# Main.net
KiCad netlist of a schematic drawn in Altium Designer
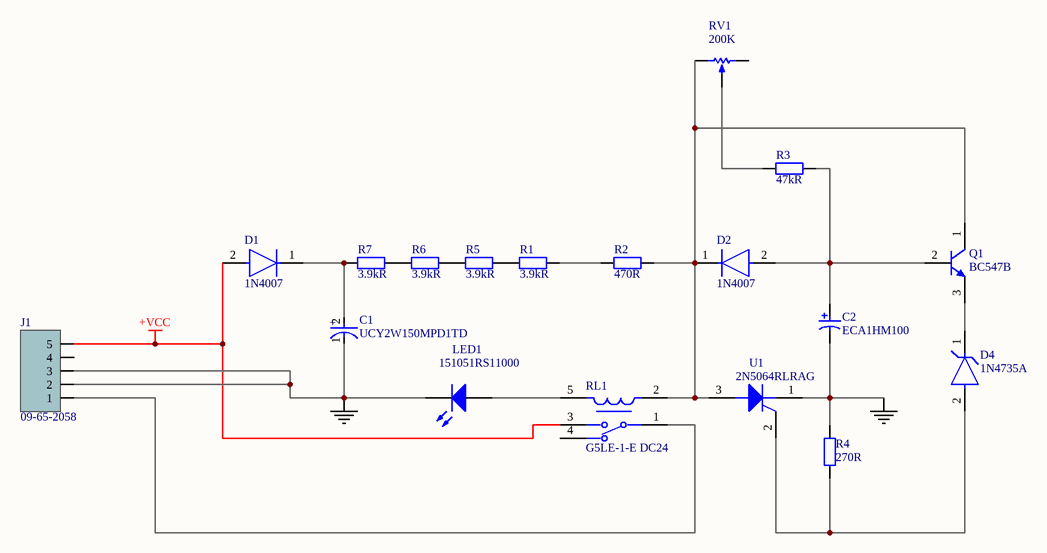
[diagram p0: Main.SchDoc]

(export (version "E")
  (design (tool "Eeschema 10.0.6"))
  (components
    (comp (ref "C1")
      (value "UCY2W150MPD1TD")
      (footprint "FP-UCY2W150MPD1TD-MFG")
      (description "CAP ALUM 15UF 20% 450V RADIAL")
      (fields (field (name "TOLERANCE") "20%"))
      (libsource (lib "Altium Content Vault") (part "a00bbbee19879c290e62620ae7e47b1"))
    )
    (comp (ref "C2")
      (value "ECA1HM100")
      (footprint "CAPPR55-200-1100X500X1200")
      (description "Aluminum Electrolytic Capacitor, 10 uF, +/- 20%, 50 V, -40 to 85 degC, 2-Pin THD, RoHS, Bulk")
      (fields (field (name "MANUFACTURER") "Panasonic") (field (name "TOLERANCE") "20%"))
      (libsource (lib "Altium Content Vault") (part "CAP-P-2"))
    )
    (comp (ref "D1")
      (value "1N4007")
      (footprint "FP-1N4007-MFG")
      (description "Rectifier diode 1000 V 1 A DO-41, ,")
      (fields
        (field (name "MANUFACTURER") "Diotec")
        (field (name "OCTOPART") "https://octopart.com/1n4007-diotec-4040411")
      )
      (libsource (lib "Altium Content Vault") (part "d7152d700b627762746794eb795d46e"))
    )
    (comp (ref "D2")
      (value "1N4007")
      (footprint "FP-1N4007-MFG")
      (description "Rectifier diode 1000 V 1 A DO-41, ,")
      (fields
        (field (name "MANUFACTURER") "Diotec")
        (field (name "OCTOPART") "https://octopart.com/1n4007-diotec-4040411")
      )
      (libsource (lib "Altium Content Vault") (part "d7152d700b627762746794eb795d46e"))
    )
    (comp (ref "D4")
      (value "1N4735A")
      (footprint "FP-017AH-MFG")
      (description "DIODE ZENER 6.2V 1W DO41")
      (fields
        (field (name "MANUFACTURER") "ON Semiconductor")
        (field (name "OCTOPART") "https://octopart.com/1n4735a-on+semiconductor-3533934")
      )
      (libsource (lib "Altium Content Vault") (part "f813f71cba58e380607f5dd3caf9714"))
    )
    (comp (ref "J1")
      (value "09652058")
      (footprint "09652058")
      (description "SPOX™ and KK® 396 Wire-to-Board Header, Vertical, with Friction Lock, 5 Circuits")
      (fields (field (name "MANUFACTURER") "Molex") (field (name "MANUFACTURER PART NUMBER") "09-65-2058"))
      (libsource (lib "Schlib") (part "09652058"))
    )
    (comp (ref "LED1")
      (value "151051RS11000")
      (footprint "Type 5mm")
      (description "THT LED round mono-color color lens, WL-TMRW, Red")
      (fields (field (name "MANUFACTURER") "Wuerth Elektronik"))
      (libsource (lib "Altium Content Vault") (part "WE-LED_K1A2-2"))
    )
    (comp (ref "Q1")
      (value "BC547B")
      (footprint "ONSC-TO-92-3-29-11")
      (description "Amplifier Transistor, NPN Silicon, 3-Pin TO-92, Bulk Box")
      (fields (field (name "MANUFACTURER") "On Semiconductor") (field (name "PARTNUMBER") "BC547C"))
      (libsource (lib "Altium Content Vault") (part "ONSC-NPN-C1B2E3-3"))
    )
    (comp (ref "R1")
      (value "PR02000203901JA100")
      (footprint "AXIAL-0.7")
      (description "PR02 Series Axial Metal Film Resistor 3.9kOhms +/-5% 2W +/-250ppm/degC")
      (fields
        (field (name "MANUFACTURER") "Vishay")
        (field (name "RESISTANCE") "3.9kR")
        (field (name "TOLERANCE") "5%")
        (field (name "PUBLISHER") "Altium Limited")
      )
      (libsource (lib "Miscellaneous Devices") (part "Res2"))
    )
    (comp (ref "R2")
      (value "470R")
      (footprint "AXIAL-0.4")
      (description "470 Ohms ±5% 0.5W, 1/2W Through Hole Resistor Axial - Metal Film")
      (fields
        (field (name "MANUFACTURER") "Vishay BCcomponents")
        (field (name "MANUFACTURER PART NUMBER") "SFR16S0004700JA500")
        (field (name "PUBLISHER") "Altium Limited")
      )
      (libsource (lib "Miscellaneous Devices") (part "Res2"))
    )
    (comp (ref "R3")
      (value "47kR")
      (footprint "AXIAL-0.4")
      (description "Res Metal Film 47K Ohm 1% 1/4W ±100ppm/°C Conformal AXL Thru-Hole T/R")
      (fields
        (field (name "MANUFACTURER") "Stackpole Electronics")
        (field (name "MANUFACTURER PART NUMBER") "RNF14FTD47K0")
        (field (name "PUBLISHER") "Altium Limited")
      )
      (libsource (lib "Miscellaneous Devices") (part "Res2"))
    )
    (comp (ref "R4")
      (value "SFR16S0002700JA500")
      (footprint "AXIAL-0.4")
      (fields
        (field (name "MANUFACTURER") "Vishay BCcomponents")
        (field (name "RESISTANCE") "270R")
        (field (name "TOLERANCE") "5%")
        (field (name "PUBLISHER") "Altium Limited")
      )
      (libsource (lib "") (part "Res2_2"))
    )
    (comp (ref "R5")
      (value "PR02000203901JA100")
      (footprint "AXIAL-0.7")
      (description "PR02 Series Axial Metal Film Resistor 3.9kOhms +/-5% 2W +/-250ppm/degC")
      (fields
        (field (name "MANUFACTURER") "Vishay")
        (field (name "RESISTANCE") "3.9kR")
        (field (name "TOLERANCE") "5%")
        (field (name "PUBLISHER") "Altium Limited")
      )
      (libsource (lib "") (part "Res2_1"))
    )
    (comp (ref "R6")
      (value "PR02000203901JA100")
      (footprint "AXIAL-0.7")
      (description "PR02 Series Axial Metal Film Resistor 3.9kOhms +/-5% 2W +/-250ppm/degC")
      (fields
        (field (name "MANUFACTURER") "Vishay")
        (field (name "RESISTANCE") "3.9kR")
        (field (name "TOLERANCE") "5%")
        (field (name "PUBLISHER") "Altium Limited")
      )
      (libsource (lib "Miscellaneous Devices") (part "Res2"))
    )
    (comp (ref "R7")
      (value "PR02000203901JA100")
      (footprint "AXIAL-0.7")
      (description "PR02 Series Axial Metal Film Resistor 3.9kOhms +/-5% 2W +/-250ppm/degC")
      (fields
        (field (name "MANUFACTURER") "Vishay")
        (field (name "RESISTANCE") "3.9kR")
        (field (name "TOLERANCE") "5%")
        (field (name "PUBLISHER") "Altium Limited")
      )
      (libsource (lib "") (part "Res2_1"))
    )
    (comp (ref "RL1")
      (value "G5LE-1-E DC24")
      (footprint "FP-G5LE-1-E_DC24-MFG")
      (description "RELAY GEN PURPOSE SPDT 16A 24V")
      (libsource (lib "Altium Content Vault") (part "c03b8d08e5d02e70a6880f365e34168"))
    )
    (comp (ref "RV1")
      (value "200K")
      (footprint "HDR1X2")
      (description "P160 Series 200 kOhm ±20 % Panel Mount Multi-Turn Potentiometer")
      (fields
        (field (name "MANUFACTURER") "TT BI")
        (field (name "MANUFACTURER PART NUMBER") "P160KNP-0QC15B200K")
        (field (name "PUBLISHER") "Altium Limited")
      )
      (libsource (lib "Miscellaneous Devices") (part "RPot"))
    )
    (comp (ref "U1")
      (value "2N5064RLRAG")
      (footprint "ONSC-TO-92-3-29-11")
      (fields (field (name "MANUFACTURER") "On Semiconductor"))
      (libsource (lib "Altium Content Vault") (part "ONSC-SCR-K1G2A3-3"))
    )
  )
  (nets
    (net (code "1") (name "+VCC") (class "Default")
      (node (ref "D1") (pin "2") (pinfunction "A_2") (pintype "passive"))
      (node (ref "J1") (pin "5") (pinfunction "5_5") (pintype "passive"))
      (node (ref "RL1") (pin "3") (pinfunction "3_3") (pintype "passive"))
    )
    (net (code "2") (name "GND") (class "Default")
      (node (ref "C1") (pin "1") (pinfunction "C_1") (pintype "passive"))
      (node (ref "C2") (pin "2") (pinfunction "2_2") (pintype "passive"))
      (node (ref "J1") (pin "2") (pinfunction "2_2") (pintype "passive"))
      (node (ref "J1") (pin "3") (pinfunction "3_3") (pintype "passive"))
      (node (ref "LED1") (pin "1") (pinfunction "K_1") (pintype "passive"))
      (node (ref "R4") (pin "2") (pinfunction "2_2") (pintype "passive"))
      (node (ref "U1") (pin "1") (pinfunction "K_1") (pintype "passive"))
    )
    (net (code "3") (name "Net-(C1-A)") (class "Default")
      (node (ref "C1") (pin "2") (pinfunction "A_2") (pintype "passive"))
      (node (ref "D1") (pin "1") (pinfunction "C_1") (pintype "passive"))
      (node (ref "R7") (pin "2") (pinfunction "2_2") (pintype "passive"))
    )
    (net (code "4") (name "Net-(D2-A)") (class "Default")
      (node (ref "C2") (pin "1") (pinfunction "1_1") (pintype "passive"))
      (node (ref "D2") (pin "2") (pinfunction "A_2") (pintype "passive"))
      (node (ref "Q1") (pin "2") (pinfunction "B_2") (pintype "passive"))
      (node (ref "R3") (pin "2") (pinfunction "2_2") (pintype "passive"))
    )
    (net (code "5") (name "Net-(D2-C)") (class "Default")
      (node (ref "D2") (pin "1") (pinfunction "C_1") (pintype "passive"))
      (node (ref "Q1") (pin "1") (pinfunction "C_1") (pintype "passive"))
      (node (ref "R2") (pin "2") (pinfunction "2_2") (pintype "passive"))
      (node (ref "RL1") (pin "2") (pinfunction "2_2") (pintype "passive"))
      (node (ref "RV1") (pin "1") (pinfunction "TOP_1") (pintype "passive"))
      (node (ref "U1") (pin "3") (pinfunction "A_3") (pintype "passive"))
    )
    (net (code "6") (name "Net-(D4-A)") (class "Default")
      (node (ref "D4") (pin "2") (pinfunction "A_2") (pintype "passive"))
      (node (ref "R4") (pin "1") (pinfunction "1_1") (pintype "passive"))
      (node (ref "U1") (pin "2") (pinfunction "G_2") (pintype "passive"))
    )
    (net (code "7") (name "Net-(D4-C)") (class "Default")
      (node (ref "D4") (pin "1") (pinfunction "C_1") (pintype "passive"))
      (node (ref "Q1") (pin "3") (pinfunction "E_3") (pintype "passive"))
    )
    (net (code "8") (name "Net-(J1-Pad1)") (class "Default")
      (node (ref "J1") (pin "1") (pinfunction "1_1") (pintype "passive"))
      (node (ref "RL1") (pin "1") (pinfunction "1_1") (pintype "passive"))
    )
    (net (code "9") (name "Net-(LED1-A)") (class "Default")
      (node (ref "LED1") (pin "2") (pinfunction "A_2") (pintype "passive"))
      (node (ref "RL1") (pin "5") (pinfunction "5_5") (pintype "passive"))
    )
    (net (code "10") (name "Net-(R1-Pad1)") (class "Default")
      (node (ref "R1") (pin "1") (pinfunction "1_1") (pintype "passive"))
      (node (ref "R5") (pin "1") (pinfunction "1_1") (pintype "passive"))
    )
    (net (code "11") (name "Net-(R1-Pad2)") (class "Default")
      (node (ref "R1") (pin "2") (pinfunction "2_2") (pintype "passive"))
      (node (ref "R2") (pin "1") (pinfunction "1_1") (pintype "passive"))
    )
    (net (code "12") (name "Net-(R5-Pad2)") (class "Default")
      (node (ref "R5") (pin "2") (pinfunction "2_2") (pintype "passive"))
      (node (ref "R6") (pin "2") (pinfunction "2_2") (pintype "passive"))
    )
    (net (code "13") (name "Net-(R6-Pad1)") (class "Default")
      (node (ref "R6") (pin "1") (pinfunction "1_1") (pintype "passive"))
      (node (ref "R7") (pin "1") (pinfunction "1_1") (pintype "passive"))
    )
    (net (code "14") (name "Net-(RV1-TAP)") (class "Default")
      (node (ref "R3") (pin "1") (pinfunction "1_1") (pintype "passive"))
      (node (ref "RV1") (pin "3") (pinfunction "TAP_3") (pintype "passive"))
    )
    (net (code "15") (name "unconnected-(J1-Pad4)") (class "Default")
      (node (ref "J1") (pin "4") (pinfunction "4_4") (pintype "passive"))
    )
    (net (code "16") (name "unconnected-(RL1-Pad4)") (class "Default")
      (node (ref "RL1") (pin "4") (pinfunction "4_4") (pintype "passive"))
    )
    (net (code "17") (name "unconnected-(RV1-BOT-Pad2)") (class "Default")
      (node (ref "RV1") (pin "2") (pinfunction "BOT_2") (pintype "passive"))
    )
  )
)
